# nRF-MCU.net
KiCad netlist of a schematic drawn in Altium Designer
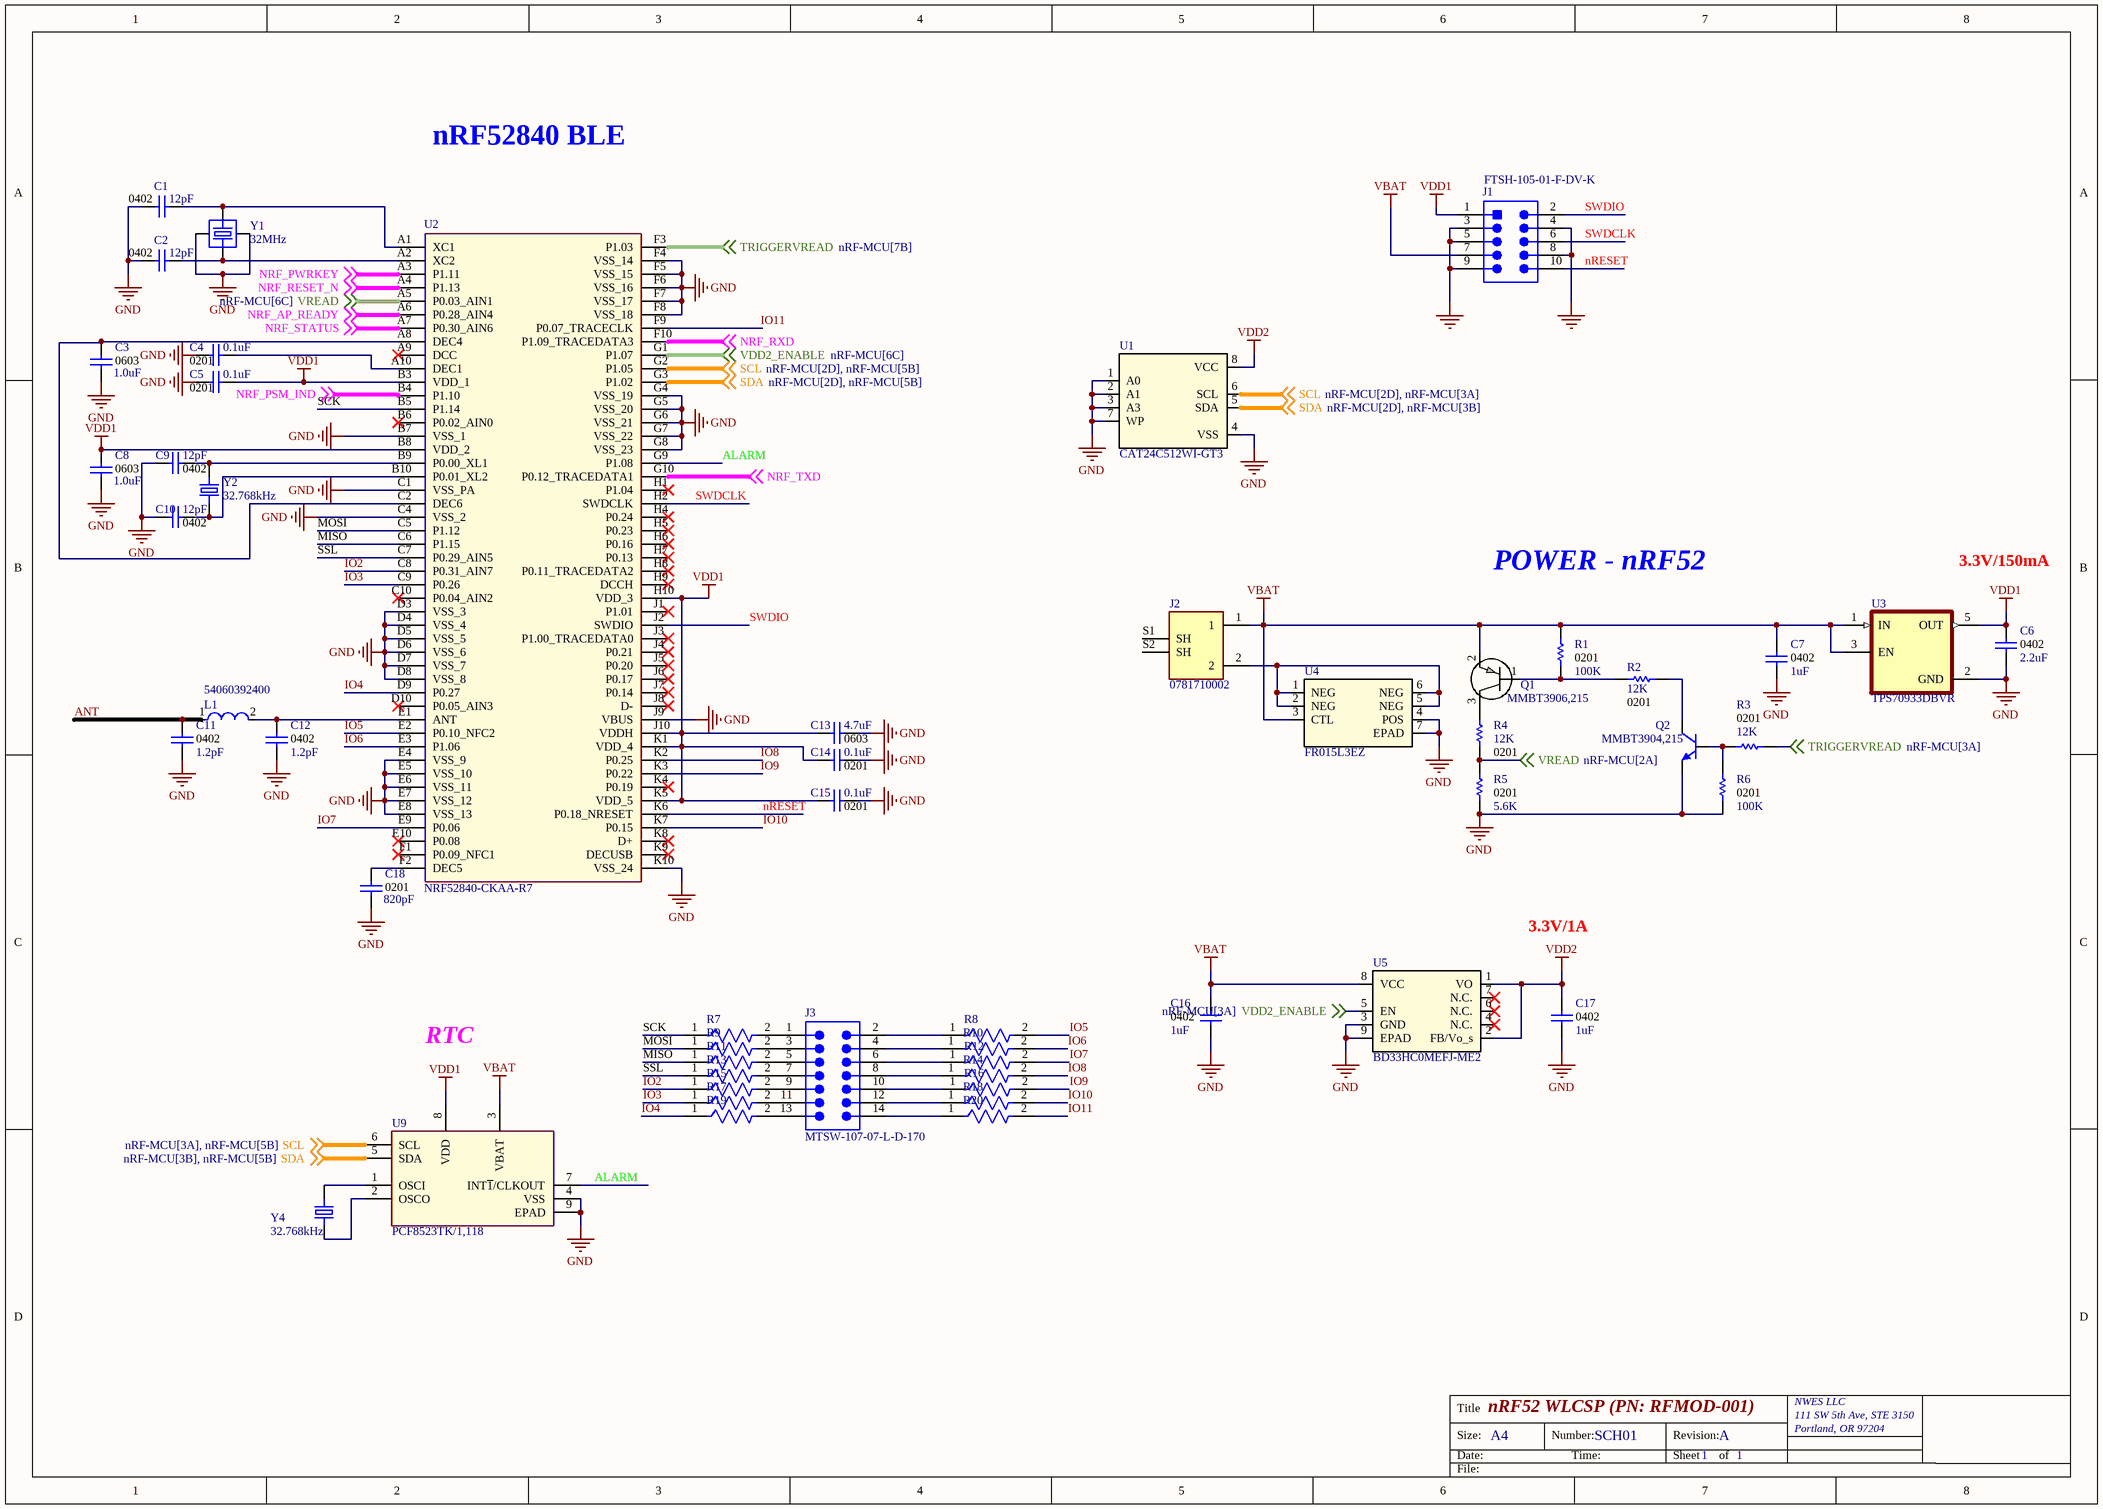
[diagram p0: nRF-MCU.SchDoc]

(export (version "E")
  (design (tool "Eeschema 10.0.6"))
  (components
    (comp (ref "C1")
      (value "12pF")
      (footprint "CAPC1005X55USR")
      (description "CAP CER 12PF 50V C0G/NP0 0402")
      (fields
        (field (name "MANUFACTURER PART NUMBER") "CC0402GRNPO9BN120")
        (field (name "MANUFACTURER") "YAGEO")
        (field (name "PACKAGE") "0402")
      )
      (libsource (lib "nRF52-Intro") (part "CAP CER 12PF 50V C0G/NP0 0402"))
    )
    (comp (ref "C2")
      (value "12pF")
      (footprint "CAPC1005X55USR")
      (description "CAP CER 12PF 50V C0G/NP0 0402")
      (fields
        (field (name "MANUFACTURER PART NUMBER") "CC0402GRNPO9BN120")
        (field (name "MANUFACTURER") "YAGEO")
        (field (name "PACKAGE") "0402")
      )
      (libsource (lib "nRF52-Intro") (part "CAP CER 12PF 50V C0G/NP0 0402"))
    )
    (comp (ref "C3")
      (value "1.0uF")
      (footprint "CAPC1608")
      (description "CAP CER 1UF 16V X7R 0603")
      (fields
        (field (name "MANUFACTURER PART NUMBER") "C0603C105K4RAC7867")
        (field (name "MANUFACTURER") "KEMET")
        (field (name "PACKAGE") "0603")
      )
      (libsource (lib "nRF52-Intro") (part "CAP CER 1UF 16V X7R 0603"))
    )
    (comp (ref "C4")
      (value "0.1uF")
      (footprint "CAPC0603X33N")
      (description "CAP CER 0.1UF 6.3V X7R 0201")
      (fields
        (field (name "MANUFACTURER PART NUMBER") "CC0201KRX7R5BB104")
        (field (name "MANUFACTURER") "YAGEO")
        (field (name "PACKAGE") "0201")
      )
      (libsource (lib "nRF52-Intro") (part "CAP CER 0.1UF 6.3V X7R 0201"))
    )
    (comp (ref "C5")
      (value "0.1uF")
      (footprint "CAPC0603X33N")
      (description "CAP CER 0.1UF 6.3V X7R 0201")
      (fields
        (field (name "MANUFACTURER PART NUMBER") "CC0201KRX7R5BB104")
        (field (name "MANUFACTURER") "YAGEO")
        (field (name "PACKAGE") "0201")
      )
      (libsource (lib "nRF52-Intro") (part "CAP CER 0.1UF 6.3V X7R 0201"))
    )
    (comp (ref "C6")
      (value "2.2uF")
      (footprint "CAPC1005X55USR")
      (description "CAP CER 2.2UF 25V X5R 0402")
      (fields
        (field (name "MANUFACTURER PART NUMBER") "GRM155R61E225ME15D")
        (field (name "MANUFACTURER") "Murata Electronics")
        (field (name "PACKAGE") "0402")
      )
      (libsource (lib "nRF52-Intro") (part "CAP CER 2.2UF 25V X5R 0402"))
    )
    (comp (ref "C7")
      (value "1uF")
      (footprint "CAPC1005X55USR")
      (description "CAP CER 1UF 25V X5R 0402")
      (fields
        (field (name "MANUFACTURER PART NUMBER") "GRM155C81E105ME11J")
        (field (name "MANUFACTURER") "Murata Electronics")
        (field (name "PACKAGE") "0402")
      )
      (libsource (lib "nRF52-Intro") (part "CAP CER 1UF 25V X5R 0402"))
    )
    (comp (ref "C8")
      (value "1.0uF")
      (footprint "CAPC1608")
      (description "CAP CER 1UF 16V X7R 0603")
      (fields
        (field (name "MANUFACTURER PART NUMBER") "C0603C105K4RAC7867")
        (field (name "MANUFACTURER") "KEMET")
        (field (name "PACKAGE") "0603")
      )
      (libsource (lib "nRF52-Intro") (part "CAP CER 1UF 16V X7R 0603"))
    )
    (comp (ref "C9")
      (value "12pF")
      (footprint "CAPC1005X55USR")
      (description "CAP CER 12PF 50V C0G/NP0 0402")
      (fields
        (field (name "MANUFACTURER PART NUMBER") "CC0402GRNPO9BN120")
        (field (name "MANUFACTURER") "YAGEO")
        (field (name "PACKAGE") "0402")
      )
      (libsource (lib "nRF52-Intro") (part "CAP CER 12PF 50V C0G/NP0 0402"))
    )
    (comp (ref "C10")
      (value "12pF")
      (footprint "CAPC1005X55USR")
      (description "CAP CER 12PF 50V C0G/NP0 0402")
      (fields
        (field (name "MANUFACTURER PART NUMBER") "CC0402GRNPO9BN120")
        (field (name "MANUFACTURER") "YAGEO")
        (field (name "PACKAGE") "0402")
      )
      (libsource (lib "nRF52-Intro") (part "CAP CER 12PF 50V C0G/NP0 0402"))
    )
    (comp (ref "C11")
      (value "1.2pF")
      (footprint "CAPC1005X55USR")
      (description "CAP CER 1.2PF 50V C0G/NP0 0402")
      (fields
        (field (name "MANUFACTURER PART NUMBER") "GCM1555C1H1R2BA16D")
        (field (name "MANUFACTURER") "Murata Electronics")
        (field (name "PACKAGE") "0402")
      )
      (libsource (lib "nRF52-Intro") (part "CAP CER 1.2PF 50V C0G/NP0 0402"))
    )
    (comp (ref "C12")
      (value "1.2pF")
      (footprint "CAPC1005X55USR")
      (description "CAP CER 1.2PF 50V C0G/NP0 0402")
      (fields
        (field (name "MANUFACTURER PART NUMBER") "GCM1555C1H1R2BA16D")
        (field (name "MANUFACTURER") "Murata Electronics")
        (field (name "PACKAGE") "0402")
      )
      (libsource (lib "nRF52-Intro") (part "CAP CER 1.2PF 50V C0G/NP0 0402"))
    )
    (comp (ref "C13")
      (value "4.7uF")
      (footprint "CAPC1608")
      (description "CAP CER 4.7UF 6.3V X7R 0603")
      (fields
        (field (name "MANUFACTURER PART NUMBER") "JMK107BB7475KA-T")
        (field (name "MANUFACTURER") "Taiyo Yuden")
        (field (name "PACKAGE") "0603")
      )
      (libsource (lib "nRF52-Intro") (part "CAP CER 4.7UF 6.3V X7R 0603"))
    )
    (comp (ref "C14")
      (value "0.1uF")
      (footprint "CAPC0603X33N")
      (description "CAP CER 0.1UF 6.3V X7R 0201")
      (fields
        (field (name "MANUFACTURER PART NUMBER") "CC0201KRX7R5BB104")
        (field (name "MANUFACTURER") "YAGEO")
        (field (name "PACKAGE") "0201")
      )
      (libsource (lib "nRF52-Intro") (part "CAP CER 0.1UF 6.3V X7R 0201"))
    )
    (comp (ref "C15")
      (value "0.1uF")
      (footprint "CAPC0603X33N")
      (description "CAP CER 0.1UF 6.3V X7R 0201")
      (fields
        (field (name "MANUFACTURER PART NUMBER") "CC0201KRX7R5BB104")
        (field (name "MANUFACTURER") "YAGEO")
        (field (name "PACKAGE") "0201")
      )
      (libsource (lib "nRF52-Intro") (part "CAP CER 0.1UF 6.3V X7R 0201"))
    )
    (comp (ref "C16")
      (value "1uF")
      (footprint "CAPC1005X55USR")
      (description "CAP CER 1UF 25V X5R 0402")
      (fields
        (field (name "MANUFACTURER PART NUMBER") "GRM155C81E105ME11J")
        (field (name "MANUFACTURER") "Murata Electronics")
        (field (name "PACKAGE") "0402")
      )
      (libsource (lib "nRF52-Intro") (part "CAP CER 1UF 25V X5R 0402"))
    )
    (comp (ref "C17")
      (value "1uF")
      (footprint "CAPC1005X55USR")
      (description "CAP CER 1UF 25V X5R 0402")
      (fields
        (field (name "MANUFACTURER PART NUMBER") "GRM155C81E105ME11J")
        (field (name "MANUFACTURER") "Murata Electronics")
        (field (name "PACKAGE") "0402")
      )
      (libsource (lib "nRF52-Intro") (part "CAP CER 1UF 25V X5R 0402"))
    )
    (comp (ref "C18")
      (value "820pF")
      (footprint "CAPC0603X33N")
      (description "CAP CER 820PF 25V X7R 0201")
      (fields
        (field (name "MANUFACTURER PART NUMBER") "CC0201KRX7R8BB821")
        (field (name "MANUFACTURER") "YAGEO")
        (field (name "PACKAGE") "0201")
      )
      (libsource (lib "nRF52-Intro") (part "CAP CER 820PF 25V X7R 0201"))
    )
    (comp (ref "J1")
      (value "FTSH-105-01-F-DV-K")
      (footprint "SMTC-FTSH-105-01-L-DV-K_V")
      (description "Male Header, Pitch 1.27 mm, 2 x 5 Position, Height 6.12 mm, RoHS, Tube")
      (fields (field (name "MANUFACTURER") "Samtec"))
      (libsource (lib "Altium Content Vault") (part "CN-2P-M-R10"))
    )
    (comp (ref "J2")
      (value "0781710002")
      (footprint "MOLEX_0781710002")
      (fields (field (name "MANUFACTURER") "Molex"))
      (libsource (lib "nRF52-Intro") (part "CONN_0781710002"))
    )
    (comp (ref "J3")
      (value "MTSW-107-07-L-D-170")
      (footprint "SMTC-MTSW-107-07-X-D-170")
      (fields (field (name "MANUFACTURER") "Samtec"))
      (libsource (lib "Altium Content Vault") (part "SMTC-MTSW-107-07-X-D-170"))
    )
    (comp (ref "L1")
      (value "54060392400")
      (footprint "FP-LQW18AN_00-MFG")
      (description "Fixed Inductors RF Chip Inductor SMD 3.9nH 0603 10% Tol")
      (fields (field (name "TOLERANCE") "2%") (field (name "MANUFACTURER") "Sumida"))
      (libsource (lib "Altium Content Vault") (part "725321dda6339637d4d059423bc1c3c"))
    )
    (comp (ref "Q1")
      (value "MMBT3906,215")
      (footprint "SOT-23")
      (description "TRANS PNP 40V 0.2A TO236AB")
      (fields (field (name "MANUFACTURER") "Nexperia"))
      (libsource (lib "nRF52-Intro") (part "PNP_MMBT3906,215"))
    )
    (comp (ref "Q2")
      (value "MMBT3904,215")
      (footprint "SOT-23")
      (description "TRANS NPN 40V 0.2A SOT23")
      (fields (field (name "MANUFACTURER") "Nexperia"))
      (libsource (lib "nRF52-Intro") (part "NPN_MMBT3904,215"))
    )
    (comp (ref "R1")
      (value "100K")
      (footprint "RESC0603X26N")
      (description "RES 100K OHM 1% 1/20W 0201")
      (fields
        (field (name "MANUFACTURER") "Yageo")
        (field (name "PACKAGE") "0201")
        (field (name "MANUFACTURER PART NUMBER") "RC0201FR-07100KL")
      )
      (libsource (lib "nRF52-Intro") (part "RES 100K OHM 1% 1/20W 0201"))
    )
    (comp (ref "R2")
      (value "12K")
      (footprint "RESC0603X26N")
      (description "RES 12K OHM 1% 1/20W 0201")
      (fields
        (field (name "MANUFACTURER") "Yageo")
        (field (name "PACKAGE") "0201")
        (field (name "MANUFACTURER PART NUMBER") "RC0201FR-0712KL")
      )
      (libsource (lib "nRF52-Intro") (part "RES 12K OHM 1% 1/20W 0201"))
    )
    (comp (ref "R3")
      (value "12K")
      (footprint "RESC0603X26N")
      (description "RES 12K OHM 1% 1/20W 0201")
      (fields
        (field (name "MANUFACTURER") "Yageo")
        (field (name "PACKAGE") "0201")
        (field (name "MANUFACTURER PART NUMBER") "RC0201FR-0712KL")
      )
      (libsource (lib "nRF52-Intro") (part "RES 12K OHM 1% 1/20W 0201"))
    )
    (comp (ref "R4")
      (value "12K")
      (footprint "RESC0603X26N")
      (description "RES 12K OHM 1% 1/20W 0201")
      (fields
        (field (name "MANUFACTURER") "Yageo")
        (field (name "PACKAGE") "0201")
        (field (name "MANUFACTURER PART NUMBER") "RC0201FR-0712KL")
      )
      (libsource (lib "nRF52-Intro") (part "RES 12K OHM 1% 1/20W 0201"))
    )
    (comp (ref "R5")
      (value "5.6K")
      (footprint "RESC0603X26N")
      (description "RES 5.6K OHM 1% 1/20W 0201")
      (fields
        (field (name "MANUFACTURER") "Yageo")
        (field (name "PACKAGE") "0201")
        (field (name "MANUFACTURER PART NUMBER") "RC0201FR-075K6L")
      )
      (libsource (lib "nRF52-Intro") (part "RES 5.6K OHM 1% 1/20W 0201"))
    )
    (comp (ref "R6")
      (value "100K")
      (footprint "RESC0603X26N")
      (description "RES 100K OHM 1% 1/20W 0201")
      (fields
        (field (name "MANUFACTURER") "Yageo")
        (field (name "PACKAGE") "0201")
        (field (name "MANUFACTURER PART NUMBER") "RC0201FR-07100KL")
      )
      (libsource (lib "nRF52-Intro") (part "RES 100K OHM 1% 1/20W 0201"))
    )
    (comp (ref "R7")
      (value "CRCW040222R0JNED")
      (footprint "FP-CRCW0402-e3-MFG")
      (description "RES Thick Film, 22Ω, 5%, 0.063W, 200ppm/°C, 0402")
      (fields (field (name "TOLERANCE") "5%"))
      (libsource (lib "Altium Content Vault") (part "1029c3af85768c4190bb7ad29bc67b5"))
    )
    (comp (ref "R8")
      (value "CRCW040222R0JNED")
      (footprint "FP-CRCW0402-e3-MFG")
      (description "RES Thick Film, 22Ω, 5%, 0.063W, 200ppm/°C, 0402")
      (fields (field (name "TOLERANCE") "5%"))
      (libsource (lib "Altium Content Vault") (part "1029c3af85768c4190bb7ad29bc67b5"))
    )
    (comp (ref "R9")
      (value "CRCW040222R0JNED")
      (footprint "FP-CRCW0402-e3-MFG")
      (description "RES Thick Film, 22Ω, 5%, 0.063W, 200ppm/°C, 0402")
      (fields (field (name "TOLERANCE") "5%"))
      (libsource (lib "Altium Content Vault") (part "1029c3af85768c4190bb7ad29bc67b5"))
    )
    (comp (ref "R10")
      (value "CRCW040222R0JNED")
      (footprint "FP-CRCW0402-e3-MFG")
      (description "RES Thick Film, 22Ω, 5%, 0.063W, 200ppm/°C, 0402")
      (fields (field (name "TOLERANCE") "5%"))
      (libsource (lib "Altium Content Vault") (part "1029c3af85768c4190bb7ad29bc67b5"))
    )
    (comp (ref "R11")
      (value "CRCW040222R0JNED")
      (footprint "FP-CRCW0402-e3-MFG")
      (description "RES Thick Film, 22Ω, 5%, 0.063W, 200ppm/°C, 0402")
      (fields (field (name "TOLERANCE") "5%"))
      (libsource (lib "Altium Content Vault") (part "1029c3af85768c4190bb7ad29bc67b5"))
    )
    (comp (ref "R12")
      (value "CRCW040222R0JNED")
      (footprint "FP-CRCW0402-e3-MFG")
      (description "RES Thick Film, 22Ω, 5%, 0.063W, 200ppm/°C, 0402")
      (fields (field (name "TOLERANCE") "5%"))
      (libsource (lib "Altium Content Vault") (part "1029c3af85768c4190bb7ad29bc67b5"))
    )
    (comp (ref "R13")
      (value "CRCW040222R0JNED")
      (footprint "FP-CRCW0402-e3-MFG")
      (description "RES Thick Film, 22Ω, 5%, 0.063W, 200ppm/°C, 0402")
      (fields (field (name "TOLERANCE") "5%"))
      (libsource (lib "Altium Content Vault") (part "1029c3af85768c4190bb7ad29bc67b5"))
    )
    (comp (ref "R14")
      (value "CRCW040222R0JNED")
      (footprint "FP-CRCW0402-e3-MFG")
      (description "RES Thick Film, 22Ω, 5%, 0.063W, 200ppm/°C, 0402")
      (fields (field (name "TOLERANCE") "5%"))
      (libsource (lib "Altium Content Vault") (part "1029c3af85768c4190bb7ad29bc67b5"))
    )
    (comp (ref "R15")
      (value "CRCW040222R0JNED")
      (footprint "FP-CRCW0402-e3-MFG")
      (description "RES Thick Film, 22Ω, 5%, 0.063W, 200ppm/°C, 0402")
      (fields (field (name "TOLERANCE") "5%"))
      (libsource (lib "Altium Content Vault") (part "1029c3af85768c4190bb7ad29bc67b5"))
    )
    (comp (ref "R16")
      (value "CRCW040222R0JNED")
      (footprint "FP-CRCW0402-e3-MFG")
      (description "RES Thick Film, 22Ω, 5%, 0.063W, 200ppm/°C, 0402")
      (fields (field (name "TOLERANCE") "5%"))
      (libsource (lib "Altium Content Vault") (part "1029c3af85768c4190bb7ad29bc67b5"))
    )
    (comp (ref "R17")
      (value "CRCW040222R0JNED")
      (footprint "FP-CRCW0402-e3-MFG")
      (description "RES Thick Film, 22Ω, 5%, 0.063W, 200ppm/°C, 0402")
      (fields (field (name "TOLERANCE") "5%"))
      (libsource (lib "Altium Content Vault") (part "1029c3af85768c4190bb7ad29bc67b5"))
    )
    (comp (ref "R18")
      (value "CRCW040222R0JNED")
      (footprint "FP-CRCW0402-e3-MFG")
      (description "RES Thick Film, 22Ω, 5%, 0.063W, 200ppm/°C, 0402")
      (fields (field (name "TOLERANCE") "5%"))
      (libsource (lib "Altium Content Vault") (part "1029c3af85768c4190bb7ad29bc67b5"))
    )
    (comp (ref "R19")
      (value "CRCW040222R0JNED")
      (footprint "FP-CRCW0402-e3-MFG")
      (description "RES Thick Film, 22Ω, 5%, 0.063W, 200ppm/°C, 0402")
      (fields (field (name "TOLERANCE") "5%"))
      (libsource (lib "Altium Content Vault") (part "1029c3af85768c4190bb7ad29bc67b5"))
    )
    (comp (ref "R20")
      (value "CRCW040222R0JNED")
      (footprint "FP-CRCW0402-e3-MFG")
      (description "RES Thick Film, 22Ω, 5%, 0.063W, 200ppm/°C, 0402")
      (fields (field (name "TOLERANCE") "5%"))
      (libsource (lib "Altium Content Vault") (part "1029c3af85768c4190bb7ad29bc67b5"))
    )
    (comp (ref "U1")
      (value "CAT24C512WI-GT3")
      (footprint "SOIC-8")
      (description "IC EEPROM 512KBIT 1MHZ 8SOIC")
      (fields (field (name "MANUFACTURER") "ON Semiconductor"))
      (libsource (lib "nRF52-Intro") (part "CAT24C512WI-GT3"))
    )
    (comp (ref "U2")
      (value "NRF52840-CKAA-R7")
      (footprint "BGA94C35P10X10_354X361X51")
      (description "Advanced Bluetooth 5, Thread and Zigbee multiprotocol SoC")
      (fields (field (name "MANUFACTURER") "Nordic Semiconductor"))
      (libsource (lib "nRF52-Intro") (part "NRF52840-CKAA-R7"))
    )
    (comp (ref "U3")
      (value "TPS70933DBVR")
      (footprint "SOT23-5")
      (description "Linear Voltage Regulator IC Positive Fixed 1 Output 3.3V 150mA SOT-23-5")
      (fields (field (name "MANUFACTURER") "Texas Instruments"))
      (libsource (lib "nRF52-Intro") (part "TPS70933DBVR"))
    )
    (comp (ref "U4")
      (value "FR015L3EZ")
      (footprint "MLP6_2X2_ONS")
      (description "LOW SIDE REV BIAS POLAR PROTECT")
      (fields (field (name "MANUFACTURER") "ON Semiconductor / Fairchild") (field (name "VOLTAGE") "1.3V"))
      (libsource (lib "nRF52-Intro") (part "FR015L3EZ"))
    )
    (comp (ref "U5")
      (value "BD33HC0MEFJ-ME2")
      (footprint "HTSOP-J8_ROM")
      (description "LDO Regulator Pos 3.3V 1A Automotive 8-Pin HTSOP-J EP T/R")
      (fields (field (name "MANUFACTURER") "Rohm"))
      (libsource (lib "nRF52-Intro") (part "BD33HC0MEFJ-ME2"))
    )
    (comp (ref "U9")
      (value "PCF8523TK/1,118")
      (footprint "HVSON80P400X400X100-9N")
      (description "PCF8523 Series 5.5 V 1 Mbps I2C Interface Real Time Clock / Calendar - HVSON-8")
      (fields (field (name "MANUFACTURER") "NXP Semiconductors"))
      (libsource (lib "HS Lockbox") (part "PCF8523TK/1,118"))
    )
    (comp (ref "Y1")
      (value "32MHz")
      (footprint "XTAL_2016_ECS_320")
      (description "Crystal 32MHz 8pF ±10ppm ±10ppm 4-Pin Miniature CSMD T/R")
      (fields
        (field (name "MANUFACTURER") "ECS International")
        (field (name "MANUFACTURER PART NUMBER") "ECS-320-8-37BQ-CKY-TR")
      )
      (libsource (lib "nRF52-Intro") (part "XTAL_ECS-320-8-37BQ-CKY-TR"))
    )
    (comp (ref "Y2")
      (value "32.768kHz")
      (footprint "XTAL_3215")
      (description "ABS07 Series 3.2 x 1.5 x 0.9 mm 32.768 KHz ±10ppm 9 pF -40 to 85°C Crystal SMT")
      (fields
        (field (name "MANUFACTURER") "Abracon")
        (field (name "MANUFACTURER PART NUMBER") "ABS07-32.768KHZ-9-1-T")
      )
      (libsource (lib "nRF52-Intro") (part "XTAL_ABS07-32.768KHZ-9-1-T"))
    )
    (comp (ref "Y4")
      (value "32.768kHz")
      (footprint "XTAL_3215")
      (description "Crystal 0.032768MHz ±20ppm (Tol) 7pF Flexural 70000Ohm 2-Pin CSMD T/R")
      (fields
        (field (name "MANUFACTURER") "Abracon")
        (field (name "MANUFACTURER PART NUMBER") "ABS07-32.768KHZ-7-T")
      )
      (libsource (lib "HS Lockbox") (part "XTAL_ABS07-32.768KHZ-7-T"))
    )
  )
  (nets
    (net (code "1") (name "/ALARM") (class "Default")
      (node (ref "U2") (pin "G9") (pinfunction "P1.08_G9") (pintype "passive"))
      (node (ref "U9") (pin "7") (pinfunction "INT~{1}/CLKOUT_7") (pintype "passive"))
    )
    (net (code "2") (name "/ANT") (class "Default")
      (node (ref "C11") (pin "2") (pinfunction "2_2") (pintype "passive"))
      (node (ref "L1") (pin "1") (pinfunction "1_1") (pintype "passive"))
    )
    (net (code "3") (name "/IO2") (class "Default")
      (node (ref "R15") (pin "1") (pinfunction "1_1") (pintype "passive"))
      (node (ref "U2") (pin "C8") (pinfunction "P0.31_AIN7_C8") (pintype "passive"))
    )
    (net (code "4") (name "/IO3") (class "Default")
      (node (ref "R17") (pin "1") (pinfunction "1_1") (pintype "passive"))
      (node (ref "U2") (pin "C9") (pinfunction "P0.26_C9") (pintype "passive"))
    )
    (net (code "5") (name "/IO4") (class "Default")
      (node (ref "R19") (pin "1") (pinfunction "1_1") (pintype "passive"))
      (node (ref "U2") (pin "D9") (pinfunction "P0.27_D9") (pintype "passive"))
    )
    (net (code "6") (name "/IO5") (class "Default")
      (node (ref "R8") (pin "2") (pinfunction "2_2") (pintype "passive"))
      (node (ref "U2") (pin "E2") (pinfunction "P0.10_NFC2_E2") (pintype "passive"))
    )
    (net (code "7") (name "/IO6") (class "Default")
      (node (ref "R10") (pin "2") (pinfunction "2_2") (pintype "passive"))
      (node (ref "U2") (pin "E3") (pinfunction "P1.06_E3") (pintype "passive"))
    )
    (net (code "8") (name "/IO7") (class "Default")
      (node (ref "R12") (pin "2") (pinfunction "2_2") (pintype "passive"))
      (node (ref "U2") (pin "E9") (pinfunction "P0.06_E9") (pintype "passive"))
    )
    (net (code "9") (name "/IO8") (class "Default")
      (node (ref "R14") (pin "2") (pinfunction "2_2") (pintype "passive"))
      (node (ref "U2") (pin "K2") (pinfunction "P0.25_K2") (pintype "passive"))
    )
    (net (code "10") (name "/IO9") (class "Default")
      (node (ref "R16") (pin "2") (pinfunction "2_2") (pintype "passive"))
      (node (ref "U2") (pin "K3") (pinfunction "P0.22_K3") (pintype "passive"))
    )
    (net (code "11") (name "/IO10") (class "Default")
      (node (ref "R18") (pin "2") (pinfunction "2_2") (pintype "passive"))
      (node (ref "U2") (pin "K7") (pinfunction "P0.15_K7") (pintype "passive"))
    )
    (net (code "12") (name "/IO11") (class "Default")
      (node (ref "R20") (pin "2") (pinfunction "2_2") (pintype "passive"))
      (node (ref "U2") (pin "F9") (pinfunction "P0.07_TRACECLK_F9") (pintype "passive"))
    )
    (net (code "13") (name "/MISO") (class "Default")
      (node (ref "R11") (pin "1") (pinfunction "1_1") (pintype "passive"))
      (node (ref "U2") (pin "C6") (pinfunction "P1.15_C6") (pintype "passive"))
    )
    (net (code "14") (name "/MOSI") (class "Default")
      (node (ref "R9") (pin "1") (pinfunction "1_1") (pintype "passive"))
      (node (ref "U2") (pin "C5") (pinfunction "P1.12_C5") (pintype "passive"))
    )
    (net (code "15") (name "/SCK") (class "Default")
      (node (ref "R7") (pin "1") (pinfunction "1_1") (pintype "passive"))
      (node (ref "U2") (pin "B5") (pinfunction "P1.14_B5") (pintype "passive"))
    )
    (net (code "16") (name "/SSL") (class "Default")
      (node (ref "R13") (pin "1") (pinfunction "1_1") (pintype "passive"))
      (node (ref "U2") (pin "C7") (pinfunction "P0.29_AIN5_C7") (pintype "passive"))
    )
    (net (code "17") (name "/SWDCLK") (class "Default")
      (node (ref "J1") (pin "6") (pinfunction "6_6") (pintype "passive"))
      (node (ref "U2") (pin "H2") (pinfunction "SWDCLK_H2") (pintype "passive"))
    )
    (net (code "18") (name "/SWDIO") (class "Default")
      (node (ref "J1") (pin "2") (pinfunction "2_2") (pintype "passive"))
      (node (ref "U2") (pin "J2") (pinfunction "SWDIO_J2") (pintype "passive"))
    )
    (net (code "19") (name "/nRESET") (class "Default")
      (node (ref "J1") (pin "10") (pinfunction "10_10") (pintype "passive"))
      (node (ref "U2") (pin "K6") (pinfunction "P0.18_NRESET_K6") (pintype "passive"))
    )
    (net (code "20") (name "GND") (class "Default")
      (node (ref "C1") (pin "2") (pinfunction "2_2") (pintype "passive"))
      (node (ref "C10") (pin "2") (pinfunction "2_2") (pintype "passive"))
      (node (ref "C11") (pin "1") (pinfunction "1_1") (pintype "passive"))
      (node (ref "C12") (pin "1") (pinfunction "1_1") (pintype "passive"))
      (node (ref "C13") (pin "1") (pinfunction "1_1") (pintype "passive"))
      (node (ref "C14") (pin "1") (pinfunction "1_1") (pintype "passive"))
      (node (ref "C15") (pin "1") (pinfunction "1_1") (pintype "passive"))
      (node (ref "C16") (pin "1") (pinfunction "1_1") (pintype "passive"))
      (node (ref "C17") (pin "1") (pinfunction "1_1") (pintype "passive"))
      (node (ref "C18") (pin "2") (pinfunction "2_2") (pintype "passive"))
      (node (ref "C2") (pin "2") (pinfunction "2_2") (pintype "passive"))
      (node (ref "C3") (pin "2") (pinfunction "2_2") (pintype "passive"))
      (node (ref "C4") (pin "2") (pinfunction "2_2") (pintype "passive"))
      (node (ref "C5") (pin "2") (pinfunction "2_2") (pintype "passive"))
      (node (ref "C6") (pin "1") (pinfunction "1_1") (pintype "passive"))
      (node (ref "C7") (pin "1") (pinfunction "1_1") (pintype "passive"))
      (node (ref "C8") (pin "2") (pinfunction "2_2") (pintype "passive"))
      (node (ref "C9") (pin "2") (pinfunction "2_2") (pintype "passive"))
      (node (ref "J1") (pin "3") (pinfunction "3_3") (pintype "passive"))
      (node (ref "J1") (pin "4") (pinfunction "4_4") (pintype "passive"))
      (node (ref "J1") (pin "5") (pinfunction "5_5") (pintype "passive"))
      (node (ref "J1") (pin "8") (pinfunction "8_8") (pintype "passive"))
      (node (ref "J1") (pin "9") (pinfunction "9_9") (pintype "passive"))
      (node (ref "Q2") (pin "2") (pinfunction "E_2") (pintype "passive"))
      (node (ref "R5") (pin "1") (pinfunction "1_1") (pintype "passive"))
      (node (ref "R6") (pin "1") (pinfunction "1_1") (pintype "passive"))
      (node (ref "U1") (pin "1") (pinfunction "A0_1") (pintype "bidirectional"))
      (node (ref "U1") (pin "2") (pinfunction "A1_2") (pintype "bidirectional"))
      (node (ref "U1") (pin "3") (pinfunction "A3_3") (pintype "bidirectional"))
      (node (ref "U1") (pin "4") (pinfunction "VSS_4") (pintype "passive"))
      (node (ref "U1") (pin "7") (pinfunction "WP_7") (pintype "passive"))
      (node (ref "U2") (pin "B7") (pinfunction "VSS_1_B7") (pintype "passive"))
      (node (ref "U2") (pin "C1") (pinfunction "VSS_PA_C1") (pintype "passive"))
      (node (ref "U2") (pin "C4") (pinfunction "VSS_2_C4") (pintype "passive"))
      (node (ref "U2") (pin "D3") (pinfunction "VSS_3_D3") (pintype "passive"))
      (node (ref "U2") (pin "D4") (pinfunction "VSS_4_D4") (pintype "passive"))
      (node (ref "U2") (pin "D5") (pinfunction "VSS_5_D5") (pintype "passive"))
      (node (ref "U2") (pin "D6") (pinfunction "VSS_6_D6") (pintype "passive"))
      (node (ref "U2") (pin "D7") (pinfunction "VSS_7_D7") (pintype "passive"))
      (node (ref "U2") (pin "D8") (pinfunction "VSS_8_D8") (pintype "passive"))
      (node (ref "U2") (pin "E4") (pinfunction "VSS_9_E4") (pintype "passive"))
      (node (ref "U2") (pin "E5") (pinfunction "VSS_10_E5") (pintype "passive"))
      (node (ref "U2") (pin "E6") (pinfunction "VSS_11_E6") (pintype "passive"))
      (node (ref "U2") (pin "E7") (pinfunction "VSS_12_E7") (pintype "passive"))
      (node (ref "U2") (pin "E8") (pinfunction "VSS_13_E8") (pintype "passive"))
      (node (ref "U2") (pin "F4") (pinfunction "VSS_14_F4") (pintype "passive"))
      (node (ref "U2") (pin "F5") (pinfunction "VSS_15_F5") (pintype "passive"))
      (node (ref "U2") (pin "F6") (pinfunction "VSS_16_F6") (pintype "passive"))
      (node (ref "U2") (pin "F7") (pinfunction "VSS_17_F7") (pintype "passive"))
      (node (ref "U2") (pin "F8") (pinfunction "VSS_18_F8") (pintype "passive"))
      (node (ref "U2") (pin "G4") (pinfunction "VSS_19_G4") (pintype "passive"))
      (node (ref "U2") (pin "G5") (pinfunction "VSS_20_G5") (pintype "passive"))
      (node (ref "U2") (pin "G6") (pinfunction "VSS_21_G6") (pintype "passive"))
      (node (ref "U2") (pin "G7") (pinfunction "VSS_22_G7") (pintype "passive"))
      (node (ref "U2") (pin "G8") (pinfunction "VSS_23_G8") (pintype "passive"))
      (node (ref "U2") (pin "J9") (pinfunction "VBUS_J9") (pintype "passive"))
      (node (ref "U2") (pin "K10") (pinfunction "VSS_24_K10") (pintype "passive"))
      (node (ref "U3") (pin "2") (pinfunction "GND_2") (pintype "power_in"))
      (node (ref "U4") (pin "4") (pinfunction "POS_4") (pintype "passive"))
      (node (ref "U4") (pin "7") (pinfunction "EPAD_7") (pintype "passive"))
      (node (ref "U5") (pin "3") (pinfunction "GND_3") (pintype "passive"))
      (node (ref "U5") (pin "9") (pinfunction "EPAD_9") (pintype "passive"))
      (node (ref "U9") (pin "4") (pinfunction "VSS_4") (pintype "passive"))
      (node (ref "U9") (pin "9") (pinfunction "EPAD_9") (pintype "passive"))
      (node (ref "Y1") (pin "2") (pinfunction "GND_2") (pintype "passive"))
      (node (ref "Y1") (pin "4") (pinfunction "GND_4") (pintype "passive"))
    )
    (net (code "21") (name "NRF_AP_READY") (class "Default")
      (node (ref "U2") (pin "A6") (pinfunction "P0.28_AIN4_A6") (pintype "passive"))
    )
    (net (code "22") (name "NRF_PSM_IND") (class "Default")
      (node (ref "U2") (pin "B4") (pinfunction "P1.10_B4") (pintype "passive"))
    )
    (net (code "23") (name "NRF_PWRKEY") (class "Default")
      (node (ref "U2") (pin "A3") (pinfunction "P1.11_A3") (pintype "passive"))
    )
    (net (code "24") (name "NRF_RESET_N") (class "Default")
      (node (ref "U2") (pin "A4") (pinfunction "P1.13_A4") (pintype "passive"))
    )
    (net (code "25") (name "NRF_RXD") (class "Default")
      (node (ref "U2") (pin "F10") (pinfunction "P1.09_TRACEDATA3_F10") (pintype "passive"))
    )
    (net (code "26") (name "NRF_STATUS") (class "Default")
      (node (ref "U2") (pin "A7") (pinfunction "P0.30_AIN6_A7") (pintype "passive"))
    )
    (net (code "27") (name "NRF_TXD") (class "Default")
      (node (ref "U2") (pin "G10") (pinfunction "P0.12_TRACEDATA1_G10") (pintype "passive"))
    )
    (net (code "28") (name "Net-(J2-Pad2)") (class "Default")
      (node (ref "J2") (pin "2") (pinfunction "2_2") (pintype "passive"))
      (node (ref "U4") (pin "1") (pinfunction "NEG_1") (pintype "passive"))
      (node (ref "U4") (pin "2") (pinfunction "NEG_2") (pintype "passive"))
      (node (ref "U4") (pin "5") (pinfunction "NEG_5") (pintype "passive"))
      (node (ref "U4") (pin "6") (pinfunction "NEG_6") (pintype "passive"))
    )
    (net (code "29") (name "Net-(J3-Pad1)") (class "Default")
      (node (ref "J3") (pin "1") (pinfunction "1_1") (pintype "passive"))
      (node (ref "R7") (pin "2") (pinfunction "2_2") (pintype "passive"))
    )
    (net (code "30") (name "Net-(J3-Pad2)") (class "Default")
      (node (ref "J3") (pin "2") (pinfunction "2_2") (pintype "passive"))
      (node (ref "R8") (pin "1") (pinfunction "1_1") (pintype "passive"))
    )
    (net (code "31") (name "Net-(J3-Pad3)") (class "Default")
      (node (ref "J3") (pin "3") (pinfunction "3_3") (pintype "passive"))
      (node (ref "R9") (pin "2") (pinfunction "2_2") (pintype "passive"))
    )
    (net (code "32") (name "Net-(J3-Pad4)") (class "Default")
      (node (ref "J3") (pin "4") (pinfunction "4_4") (pintype "passive"))
      (node (ref "R10") (pin "1") (pinfunction "1_1") (pintype "passive"))
    )
    (net (code "33") (name "Net-(J3-Pad5)") (class "Default")
      (node (ref "J3") (pin "5") (pinfunction "5_5") (pintype "passive"))
      (node (ref "R11") (pin "2") (pinfunction "2_2") (pintype "passive"))
    )
    (net (code "34") (name "Net-(J3-Pad6)") (class "Default")
      (node (ref "J3") (pin "6") (pinfunction "6_6") (pintype "passive"))
      (node (ref "R12") (pin "1") (pinfunction "1_1") (pintype "passive"))
    )
    (net (code "35") (name "Net-(J3-Pad7)") (class "Default")
      (node (ref "J3") (pin "7") (pinfunction "7_7") (pintype "passive"))
      (node (ref "R13") (pin "2") (pinfunction "2_2") (pintype "passive"))
    )
    (net (code "36") (name "Net-(J3-Pad8)") (class "Default")
      (node (ref "J3") (pin "8") (pinfunction "8_8") (pintype "passive"))
      (node (ref "R14") (pin "1") (pinfunction "1_1") (pintype "passive"))
    )
    (net (code "37") (name "Net-(J3-Pad9)") (class "Default")
      (node (ref "J3") (pin "9") (pinfunction "9_9") (pintype "passive"))
      (node (ref "R15") (pin "2") (pinfunction "2_2") (pintype "passive"))
    )
    (net (code "38") (name "Net-(J3-Pad10)") (class "Default")
      (node (ref "J3") (pin "10") (pinfunction "10_10") (pintype "passive"))
      (node (ref "R16") (pin "1") (pinfunction "1_1") (pintype "passive"))
    )
    (net (code "39") (name "Net-(J3-Pad11)") (class "Default")
      (node (ref "J3") (pin "11") (pinfunction "11_11") (pintype "passive"))
      (node (ref "R17") (pin "2") (pinfunction "2_2") (pintype "passive"))
    )
    (net (code "40") (name "Net-(J3-Pad12)") (class "Default")
      (node (ref "J3") (pin "12") (pinfunction "12_12") (pintype "passive"))
      (node (ref "R18") (pin "1") (pinfunction "1_1") (pintype "passive"))
    )
    (net (code "41") (name "Net-(J3-Pad13)") (class "Default")
      (node (ref "J3") (pin "13") (pinfunction "13_13") (pintype "passive"))
      (node (ref "R19") (pin "2") (pinfunction "2_2") (pintype "passive"))
    )
    (net (code "42") (name "Net-(J3-Pad14)") (class "Default")
      (node (ref "J3") (pin "14") (pinfunction "14_14") (pintype "passive"))
      (node (ref "R20") (pin "1") (pinfunction "1_1") (pintype "passive"))
    )
    (net (code "43") (name "Net-(Q1-B)") (class "Default")
      (node (ref "Q1") (pin "1") (pinfunction "B_1") (pintype "passive"))
      (node (ref "R1") (pin "1") (pinfunction "1_1") (pintype "passive"))
      (node (ref "R2") (pin "2") (pinfunction "2_2") (pintype "passive"))
    )
    (net (code "44") (name "Net-(Q1-C)") (class "Default")
      (node (ref "Q1") (pin "3") (pinfunction "C_3") (pintype "passive"))
      (node (ref "R4") (pin "1") (pinfunction "1_1") (pintype "passive"))
    )
    (net (code "45") (name "Net-(Q2-B)") (class "Default")
      (node (ref "Q2") (pin "1") (pinfunction "B_1") (pintype "passive"))
      (node (ref "R3") (pin "2") (pinfunction "2_2") (pintype "passive"))
      (node (ref "R6") (pin "2") (pinfunction "2_2") (pintype "passive"))
    )
    (net (code "46") (name "Net-(Q2-C)") (class "Default")
      (node (ref "Q2") (pin "3") (pinfunction "C_3") (pintype "passive"))
      (node (ref "R2") (pin "1") (pinfunction "1_1") (pintype "passive"))
    )
    (net (code "47") (name "Net-(U2-ANT)") (class "Default")
      (node (ref "C12") (pin "2") (pinfunction "2_2") (pintype "passive"))
      (node (ref "L1") (pin "2") (pinfunction "2_2") (pintype "passive"))
      (node (ref "U2") (pin "E1") (pinfunction "ANT_E1") (pintype "passive"))
    )
    (net (code "48") (name "Net-(U2-DEC1)") (class "Default")
      (node (ref "C4") (pin "1") (pinfunction "1_1") (pintype "passive"))
      (node (ref "U2") (pin "A10") (pinfunction "DEC1_A10") (pintype "passive"))
    )
    (net (code "49") (name "Net-(U2-DEC4)") (class "Default")
      (node (ref "C3") (pin "1") (pinfunction "1_1") (pintype "passive"))
      (node (ref "U2") (pin "A8") (pinfunction "DEC4_A8") (pintype "passive"))
      (node (ref "U2") (pin "C2") (pinfunction "DEC6_C2") (pintype "passive"))
    )
    (net (code "50") (name "Net-(U2-DEC5)") (class "Default")
      (node (ref "C18") (pin "1") (pinfunction "1_1") (pintype "passive"))
      (node (ref "U2") (pin "F2") (pinfunction "DEC5_F2") (pintype "passive"))
    )
    (net (code "51") (name "Net-(U2-P0.00_XL1)") (class "Default")
      (node (ref "C9") (pin "1") (pinfunction "1_1") (pintype "passive"))
      (node (ref "U2") (pin "B9") (pinfunction "P0.00_XL1_B9") (pintype "passive"))
      (node (ref "Y2") (pin "2") (pinfunction "O/I_2") (pintype "passive"))
    )
    (net (code "52") (name "Net-(U2-P0.01_XL2)") (class "Default")
      (node (ref "C10") (pin "1") (pinfunction "1_1") (pintype "passive"))
      (node (ref "U2") (pin "B10") (pinfunction "P0.01_XL2_B10") (pintype "passive"))
      (node (ref "Y2") (pin "1") (pinfunction "I/O_1") (pintype "passive"))
    )
    (net (code "53") (name "Net-(U2-XC1)") (class "Default")
      (node (ref "C1") (pin "1") (pinfunction "1_1") (pintype "passive"))
      (node (ref "U2") (pin "A1") (pinfunction "XC1_A1") (pintype "passive"))
      (node (ref "Y1") (pin "1") (pinfunction "I/O_1") (pintype "passive"))
    )
    (net (code "54") (name "Net-(U2-XC2)") (class "Default")
      (node (ref "C2") (pin "1") (pinfunction "1_1") (pintype "passive"))
      (node (ref "U2") (pin "A2") (pinfunction "XC2_A2") (pintype "passive"))
      (node (ref "Y1") (pin "3") (pinfunction "O/I_3") (pintype "passive"))
    )
    (net (code "55") (name "Net-(U9-OSCI)") (class "Default")
      (node (ref "U9") (pin "1") (pinfunction "OSCI_1") (pintype "passive"))
      (node (ref "Y4") (pin "2") (pinfunction "O/I_2") (pintype "passive"))
    )
    (net (code "56") (name "Net-(U9-OSCO)") (class "Default")
      (node (ref "U9") (pin "2") (pinfunction "OSCO_2") (pintype "passive"))
      (node (ref "Y4") (pin "1") (pinfunction "I/O_1") (pintype "passive"))
    )
    (net (code "57") (name "SCL") (class "Default")
      (node (ref "U1") (pin "6") (pinfunction "SCL_6") (pintype "passive"))
      (node (ref "U2") (pin "G2") (pinfunction "P1.05_G2") (pintype "passive"))
      (node (ref "U9") (pin "6") (pinfunction "SCL_6") (pintype "passive"))
    )
    (net (code "58") (name "SDA") (class "Default")
      (node (ref "U1") (pin "5") (pinfunction "SDA_5") (pintype "passive"))
      (node (ref "U2") (pin "G3") (pinfunction "P1.02_G3") (pintype "passive"))
      (node (ref "U9") (pin "5") (pinfunction "SDA_5") (pintype "passive"))
    )
    (net (code "59") (name "TRIGGERVREAD") (class "Default")
      (node (ref "R3") (pin "1") (pinfunction "1_1") (pintype "passive"))
      (node (ref "U2") (pin "F3") (pinfunction "P1.03_F3") (pintype "passive"))
    )
    (net (code "60") (name "VBAT") (class "Default")
      (node (ref "C16") (pin "2") (pinfunction "2_2") (pintype "passive"))
      (node (ref "C7") (pin "2") (pinfunction "2_2") (pintype "passive"))
      (node (ref "J1") (pin "7") (pinfunction "7_7") (pintype "passive"))
      (node (ref "J2") (pin "1") (pinfunction "1_1") (pintype "passive"))
      (node (ref "Q1") (pin "2") (pinfunction "E_2") (pintype "passive"))
      (node (ref "R1") (pin "2") (pinfunction "2_2") (pintype "passive"))
      (node (ref "U3") (pin "1") (pinfunction "IN_1") (pintype "input"))
      (node (ref "U3") (pin "3") (pinfunction "EN_3") (pintype "passive"))
      (node (ref "U4") (pin "3") (pinfunction "CTL_3") (pintype "passive"))
      (node (ref "U5") (pin "8") (pinfunction "VCC_8") (pintype "passive"))
      (node (ref "U9") (pin "3") (pinfunction "VBAT_3") (pintype "passive"))
    )
    (net (code "61") (name "VDD1") (class "Default")
      (node (ref "C13") (pin "2") (pinfunction "2_2") (pintype "passive"))
      (node (ref "C14") (pin "2") (pinfunction "2_2") (pintype "passive"))
      (node (ref "C15") (pin "2") (pinfunction "2_2") (pintype "passive"))
      (node (ref "C5") (pin "1") (pinfunction "1_1") (pintype "passive"))
      (node (ref "C6") (pin "2") (pinfunction "2_2") (pintype "passive"))
      (node (ref "C8") (pin "1") (pinfunction "1_1") (pintype "passive"))
      (node (ref "J1") (pin "1") (pinfunction "1_1") (pintype "passive"))
      (node (ref "U2") (pin "B3") (pinfunction "VDD_1_B3") (pintype "passive"))
      (node (ref "U2") (pin "B8") (pinfunction "VDD_2_B8") (pintype "passive"))
      (node (ref "U2") (pin "H10") (pinfunction "VDD_3_H10") (pintype "passive"))
      (node (ref "U2") (pin "J10") (pinfunction "VDDH_J10") (pintype "passive"))
      (node (ref "U2") (pin "K1") (pinfunction "VDD_4_K1") (pintype "passive"))
      (node (ref "U2") (pin "K5") (pinfunction "VDD_5_K5") (pintype "passive"))
      (node (ref "U3") (pin "5") (pinfunction "OUT_5") (pintype "output"))
      (node (ref "U9") (pin "8") (pinfunction "VDD_8") (pintype "passive"))
    )
    (net (code "62") (name "VDD2") (class "Default")
      (node (ref "C17") (pin "2") (pinfunction "2_2") (pintype "passive"))
      (node (ref "U1") (pin "8") (pinfunction "VCC_8") (pintype "power_in"))
      (node (ref "U5") (pin "1") (pinfunction "VO_1") (pintype "passive"))
      (node (ref "U5") (pin "2") (pinfunction "FB/Vo_s_2") (pintype "passive"))
    )
    (net (code "63") (name "VDD2_ENABLE") (class "Default")
      (node (ref "U2") (pin "G1") (pinfunction "P1.07_G1") (pintype "passive"))
      (node (ref "U5") (pin "5") (pinfunction "EN_5") (pintype "passive"))
    )
    (net (code "64") (name "VREAD") (class "Default")
      (node (ref "R4") (pin "2") (pinfunction "2_2") (pintype "passive"))
      (node (ref "R5") (pin "2") (pinfunction "2_2") (pintype "passive"))
      (node (ref "U2") (pin "A5") (pinfunction "P0.03_AIN1_A5") (pintype "passive"))
    )
    (net (code "65") (name "unconnected-(J2-SH-PadS1)") (class "Default")
      (node (ref "J2") (pin "S1") (pinfunction "SH_S1") (pintype "passive"))
    )
    (net (code "66") (name "unconnected-(J2-SH-PadS2)") (class "Default")
      (node (ref "J2") (pin "S2") (pinfunction "SH_S2") (pintype "passive"))
    )
    (net (code "67") (name "unconnected-(U2-D+-PadK8)") (class "Default")
      (node (ref "U2") (pin "K8") (pinfunction "D+_K8") (pintype "passive+no_connect"))
    )
    (net (code "68") (name "unconnected-(U2-D--PadJ8)") (class "Default")
      (node (ref "U2") (pin "J8") (pinfunction "D-_J8") (pintype "passive+no_connect"))
    )
    (net (code "69") (name "unconnected-(U2-DCC-PadA9)") (class "Default")
      (node (ref "U2") (pin "A9") (pinfunction "DCC_A9") (pintype "passive+no_connect"))
    )
    (net (code "70") (name "unconnected-(U2-DCCH-PadH9)") (class "Default")
      (node (ref "U2") (pin "H9") (pinfunction "DCCH_H9") (pintype "passive+no_connect"))
    )
    (net (code "71") (name "unconnected-(U2-DECUSB-PadK9)") (class "Default")
      (node (ref "U2") (pin "K9") (pinfunction "DECUSB_K9") (pintype "passive+no_connect"))
    )
    (net (code "72") (name "unconnected-(U2-P0.02_AIN0-PadB6)") (class "Default")
      (node (ref "U2") (pin "B6") (pinfunction "P0.02_AIN0_B6") (pintype "passive+no_connect"))
    )
    (net (code "73") (name "unconnected-(U2-P0.04_AIN2-PadC10)") (class "Default")
      (node (ref "U2") (pin "C10") (pinfunction "P0.04_AIN2_C10") (pintype "passive+no_connect"))
    )
    (net (code "74") (name "unconnected-(U2-P0.05_AIN3-PadD10)") (class "Default")
      (node (ref "U2") (pin "D10") (pinfunction "P0.05_AIN3_D10") (pintype "passive+no_connect"))
    )
    (net (code "75") (name "unconnected-(U2-P0.08-PadE10)") (class "Default")
      (node (ref "U2") (pin "E10") (pinfunction "P0.08_E10") (pintype "passive+no_connect"))
    )
    (net (code "76") (name "unconnected-(U2-P0.09_NFC1-PadF1)") (class "Default")
      (node (ref "U2") (pin "F1") (pinfunction "P0.09_NFC1_F1") (pintype "passive+no_connect"))
    )
    (net (code "77") (name "unconnected-(U2-P0.11_TRACEDATA2-PadH8)") (class "Default")
      (node (ref "U2") (pin "H8") (pinfunction "P0.11_TRACEDATA2_H8") (pintype "passive+no_connect"))
    )
    (net (code "78") (name "unconnected-(U2-P0.13-PadH7)") (class "Default")
      (node (ref "U2") (pin "H7") (pinfunction "P0.13_H7") (pintype "passive+no_connect"))
    )
    (net (code "79") (name "unconnected-(U2-P0.14-PadJ7)") (class "Default")
      (node (ref "U2") (pin "J7") (pinfunction "P0.14_J7") (pintype "passive+no_connect"))
    )
    (net (code "80") (name "unconnected-(U2-P0.16-PadH6)") (class "Default")
      (node (ref "U2") (pin "H6") (pinfunction "P0.16_H6") (pintype "passive+no_connect"))
    )
    (net (code "81") (name "unconnected-(U2-P0.17-PadJ6)") (class "Default")
      (node (ref "U2") (pin "J6") (pinfunction "P0.17_J6") (pintype "passive+no_connect"))
    )
    (net (code "82") (name "unconnected-(U2-P0.19-PadK4)") (class "Default")
      (node (ref "U2") (pin "K4") (pinfunction "P0.19_K4") (pintype "passive+no_connect"))
    )
    (net (code "83") (name "unconnected-(U2-P0.20-PadJ5)") (class "Default")
      (node (ref "U2") (pin "J5") (pinfunction "P0.20_J5") (pintype "passive+no_connect"))
    )
    (net (code "84") (name "unconnected-(U2-P0.21-PadJ4)") (class "Default")
      (node (ref "U2") (pin "J4") (pinfunction "P0.21_J4") (pintype "passive+no_connect"))
    )
    (net (code "85") (name "unconnected-(U2-P0.23-PadH5)") (class "Default")
      (node (ref "U2") (pin "H5") (pinfunction "P0.23_H5") (pintype "passive+no_connect"))
    )
    (net (code "86") (name "unconnected-(U2-P0.24-PadH4)") (class "Default")
      (node (ref "U2") (pin "H4") (pinfunction "P0.24_H4") (pintype "passive+no_connect"))
    )
    (net (code "87") (name "unconnected-(U2-P1.00_TRACEDATA0-PadJ3)") (class "Default")
      (node (ref "U2") (pin "J3") (pinfunction "P1.00_TRACEDATA0_J3") (pintype "passive+no_connect"))
    )
    (net (code "88") (name "unconnected-(U2-P1.01-PadJ1)") (class "Default")
      (node (ref "U2") (pin "J1") (pinfunction "P1.01_J1") (pintype "passive+no_connect"))
    )
    (net (code "89") (name "unconnected-(U2-P1.04-PadH1)") (class "Default")
      (node (ref "U2") (pin "H1") (pinfunction "P1.04_H1") (pintype "passive+no_connect"))
    )
    (net (code "90") (name "unconnected-(U5-N.C.-Pad4)") (class "Default")
      (node (ref "U5") (pin "4") (pinfunction "N.C._4") (pintype "passive+no_connect"))
    )
    (net (code "91") (name "unconnected-(U5-N.C.-Pad6)") (class "Default")
      (node (ref "U5") (pin "6") (pinfunction "N.C._6") (pintype "passive+no_connect"))
    )
    (net (code "92") (name "unconnected-(U5-N.C.-Pad7)") (class "Default")
      (node (ref "U5") (pin "7") (pinfunction "N.C._7") (pintype "passive+no_connect"))
    )
  )
)
